# Adafruit_TPS61040_Boost_Converter.net
KiCad netlist of a schematic drawn in EAGLE
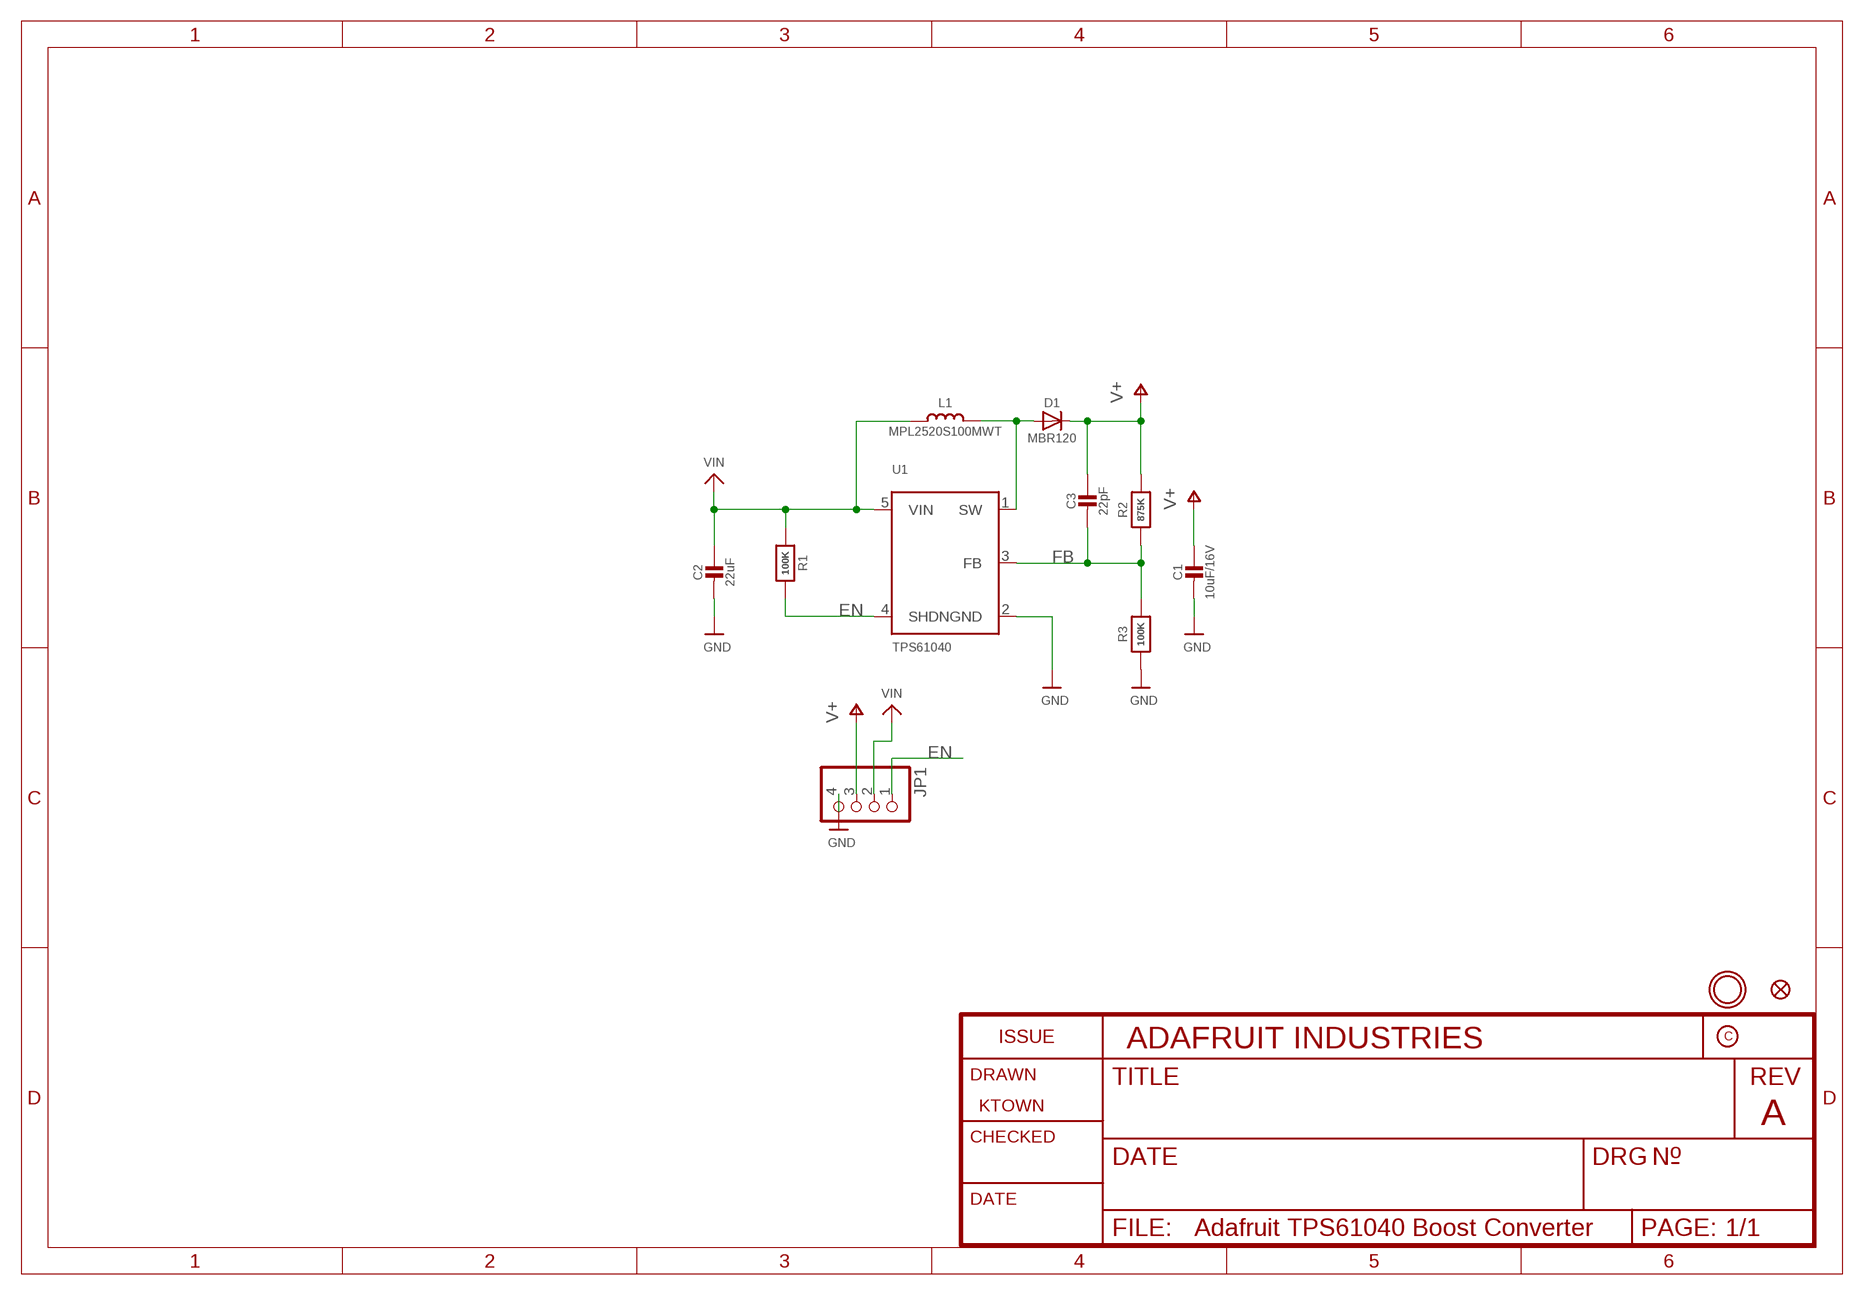
[diagram p0: schematic, sheet 1]

(export (version "E")
  (design (tool "Eeschema 10.0.6"))
  (components
    (comp (ref "C1")
      (value "10uF/16V")
      (footprint "eagle-import:0805-NO")
      (libsource (lib "eagle-import") (part "CAP_CERAMIC0805-NOOUTLINE"))
    )
    (comp (ref "C2")
      (value "22uF")
      (footprint "eagle-import:0805-NO")
      (libsource (lib "eagle-import") (part "CAP_CERAMIC0805-NOOUTLINE"))
    )
    (comp (ref "C3")
      (value "22pF")
      (footprint "eagle-import:0603-NO")
      (libsource (lib "eagle-import") (part "CAP_CERAMIC0603_NO"))
    )
    (comp (ref "D1")
      (value "MBR120")
      (footprint "eagle-import:SOD-123FL")
      (libsource (lib "eagle-import") (part "DIODE_MINISOD123"))
    )
    (comp (ref "FID1")
      (value "FIDUCIAL_1MM")
      (footprint "eagle-import:FIDUCIAL_1MM")
      (libsource (lib "eagle-import") (part "FIDUCIAL_1MM"))
    )
    (comp (ref "JP1")
      (value "HEADER-1X4ROUND")
      (footprint "eagle-import:1X04_ROUND")
      (libsource (lib "eagle-import") (part "HEADER-1X4ROUND"))
    )
    (comp (ref "L1")
      (value "MPL2520S100MWT")
      (footprint "eagle-import:INDUCTOR_1007")
      (libsource (lib "eagle-import") (part "INDUCTOR"))
    )
    (comp (ref "R1")
      (value "100K")
      (footprint "eagle-import:0603-NO")
      (libsource (lib "eagle-import") (part "RESISTOR_0603_NOOUT"))
    )
    (comp (ref "R2")
      (value "875K")
      (footprint "eagle-import:0603-NO")
      (libsource (lib "eagle-import") (part "RESISTOR_0603_NOOUT"))
    )
    (comp (ref "R3")
      (value "100K")
      (footprint "eagle-import:0603-NO")
      (libsource (lib "eagle-import") (part "RESISTOR_0603_NOOUT"))
    )
    (comp (ref "U$9")
      (value "MOUNTINGHOLE2.5")
      (footprint "eagle-import:MOUNTINGHOLE_2.5_PLATED")
      (libsource (lib "eagle-import") (part "MOUNTINGHOLE2.5"))
    )
    (comp (ref "U1")
      (value "TPS61040")
      (footprint "eagle-import:SOT23-5")
      (libsource (lib "eagle-import") (part "VREG_FAN5331"))
    )
  )
  (nets
    (net (code "1") (name "/EN") (class "Default")
      (node (ref "JP1") (pin "1") (pinfunction "1_1") (pintype "passive"))
      (node (ref "R1") (pin "2") (pinfunction "2_2") (pintype "passive"))
      (node (ref "U1") (pin "4") (pinfunction "SHDN_4") (pintype "bidirectional"))
    )
    (net (code "2") (name "/FB") (class "Default")
      (node (ref "C3") (pin "2") (pinfunction "2_2") (pintype "passive"))
      (node (ref "R2") (pin "1") (pinfunction "1_1") (pintype "passive"))
      (node (ref "R3") (pin "2") (pinfunction "2_2") (pintype "passive"))
      (node (ref "U1") (pin "3") (pinfunction "FB_3") (pintype "bidirectional"))
    )
    (net (code "3") (name "GND") (class "Default")
      (node (ref "C1") (pin "2") (pinfunction "2_2") (pintype "passive"))
      (node (ref "C2") (pin "2") (pinfunction "2_2") (pintype "passive"))
      (node (ref "JP1") (pin "4") (pinfunction "4_4") (pintype "passive"))
      (node (ref "R3") (pin "1") (pinfunction "1_1") (pintype "passive"))
      (node (ref "U1") (pin "2") (pinfunction "GND_2") (pintype "bidirectional"))
    )
    (net (code "4") (name "Net-(L1-2)") (class "Default")
      (node (ref "D1") (pin "A") (pinfunction "A_A") (pintype "passive"))
      (node (ref "L1") (pin "P$2") (pinfunction "2_P$2") (pintype "passive"))
      (node (ref "U1") (pin "1") (pinfunction "SW_1") (pintype "bidirectional"))
    )
    (net (code "5") (name "V+") (class "Default")
      (node (ref "C1") (pin "1") (pinfunction "1_1") (pintype "passive"))
      (node (ref "C3") (pin "1") (pinfunction "1_1") (pintype "passive"))
      (node (ref "D1") (pin "C") (pinfunction "C_C") (pintype "passive"))
      (node (ref "JP1") (pin "3") (pinfunction "3_3") (pintype "passive"))
      (node (ref "R2") (pin "2") (pinfunction "2_2") (pintype "passive"))
    )
    (net (code "6") (name "VIN") (class "Default")
      (node (ref "C2") (pin "1") (pinfunction "1_1") (pintype "passive"))
      (node (ref "JP1") (pin "2") (pinfunction "2_2") (pintype "passive"))
      (node (ref "L1") (pin "P$1") (pinfunction "1_P$1") (pintype "passive"))
      (node (ref "R1") (pin "1") (pinfunction "1_1") (pintype "passive"))
      (node (ref "U1") (pin "5") (pinfunction "VIN_5") (pintype "bidirectional"))
    )
  )
)
